# M_B_adapter.net
KiCad netlist of a schematic drawn in EAGLE
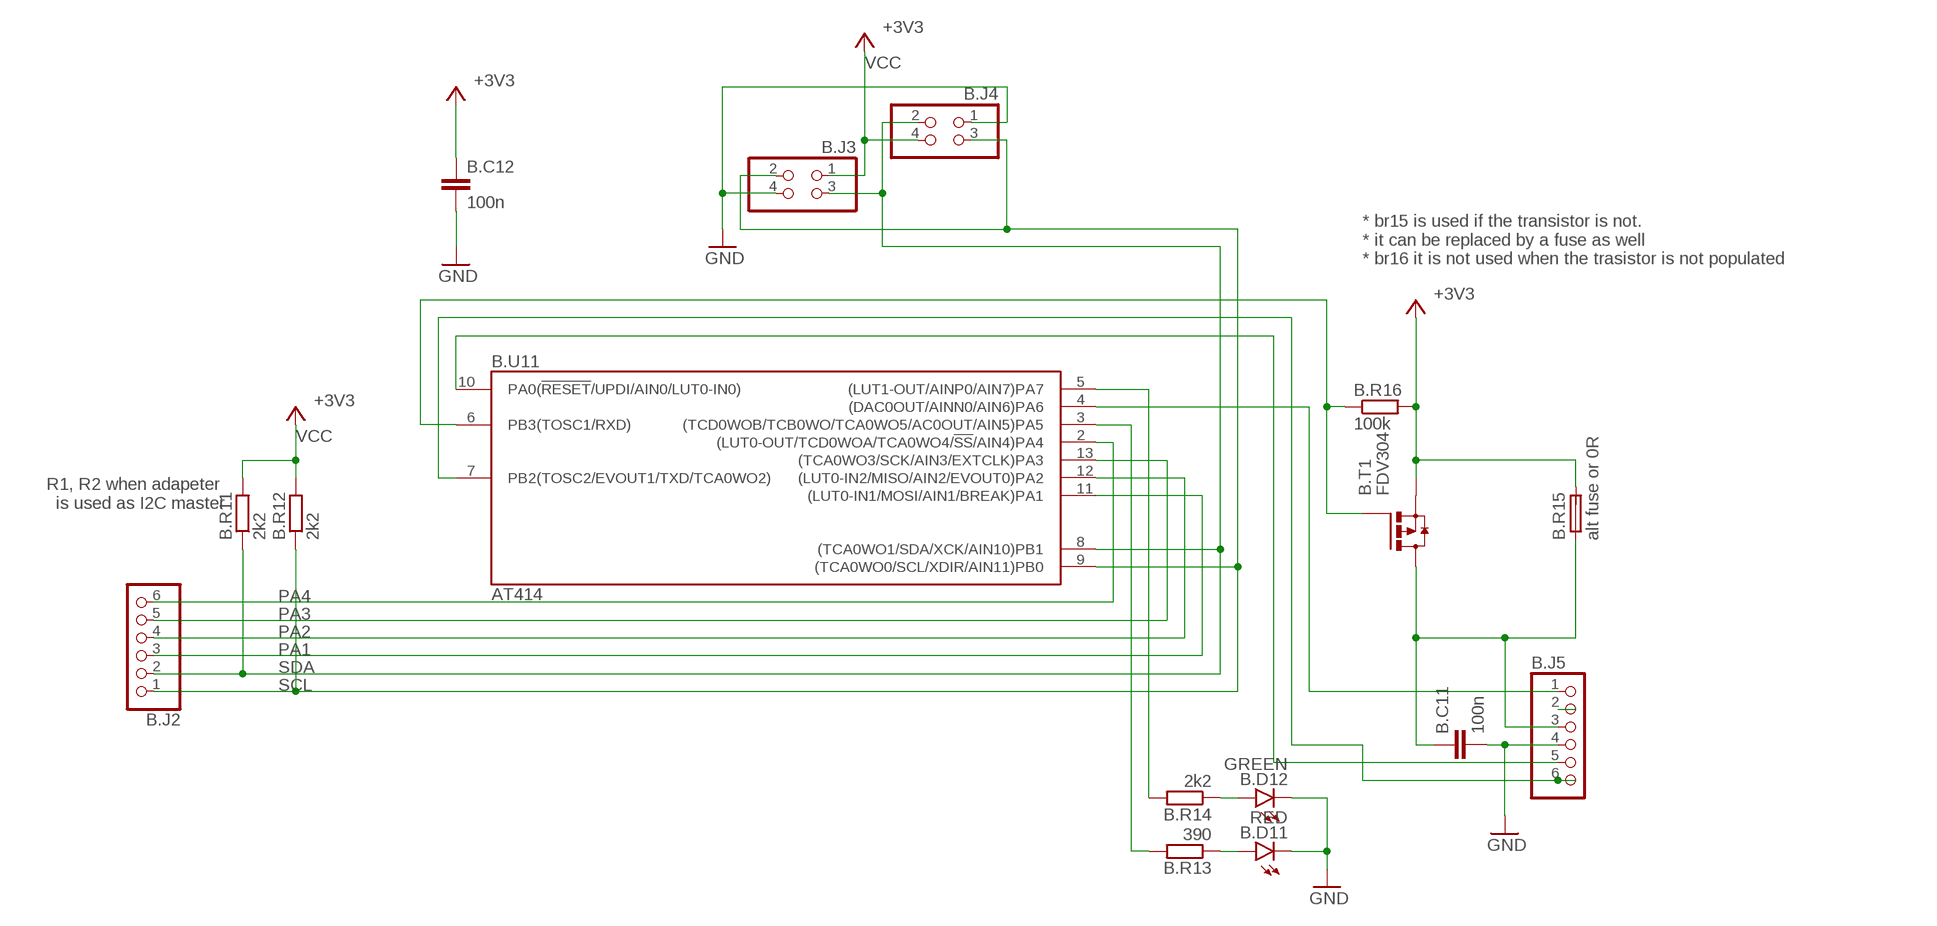
[diagram p0: schematic, sheet 1]

(export (version "E")
  (design (tool "Eeschema 10.0.6"))
  (components
    (comp (ref "B.C11")
      (value "100n")
      (footprint "eagle-import:C0603")
      (libsource (lib "eagle-import") (part "C-EUC0603"))
    )
    (comp (ref "B.C12")
      (value "100n")
      (footprint "eagle-import:C0603")
      (libsource (lib "eagle-import") (part "C-EUC0603"))
    )
    (comp (ref "B.D11")
      (value "RED")
      (footprint "eagle-import:CHIP-LED0603")
      (libsource (lib "eagle-import") (part "LEDCHIP-LED0603"))
    )
    (comp (ref "B.D12")
      (value "GREEN")
      (footprint "eagle-import:CHIP-LED0603")
      (libsource (lib "eagle-import") (part "LEDCHIP-LED0603"))
    )
    (comp (ref "B.J2")
      (value "PINHD-1X6")
      (footprint "eagle-import:1X06")
      (libsource (lib "eagle-import") (part "PINHD-1X6"))
    )
    (comp (ref "B.J3")
      (value "PINHD-2X2")
      (footprint "eagle-import:2X02")
      (libsource (lib "eagle-import") (part "PINHD-2X2"))
    )
    (comp (ref "B.J4")
      (value "PINHD-2X2")
      (footprint "eagle-import:2X02")
      (libsource (lib "eagle-import") (part "PINHD-2X2"))
    )
    (comp (ref "B.J5")
      (value "PINHD-1X6")
      (footprint "eagle-import:1X06")
      (libsource (lib "eagle-import") (part "PINHD-1X6"))
    )
    (comp (ref "B.R11")
      (value "2k2")
      (footprint "eagle-import:R0603")
      (libsource (lib "eagle-import") (part "R-EU_R0603"))
    )
    (comp (ref "B.R12")
      (value "2k2")
      (footprint "eagle-import:R0603")
      (libsource (lib "eagle-import") (part "R-EU_R0603"))
    )
    (comp (ref "B.R13")
      (value "390")
      (footprint "eagle-import:R0603")
      (libsource (lib "eagle-import") (part "R-EU_R0603"))
    )
    (comp (ref "B.R14")
      (value "2k2")
      (footprint "eagle-import:R0603")
      (libsource (lib "eagle-import") (part "R-EU_R0603"))
    )
    (comp (ref "B.R15")
      (value "alt fuse or 0R")
      (footprint "eagle-import:FUSE")
      (libsource (lib "eagle-import") (part "FUSE"))
    )
    (comp (ref "B.R16")
      (value "100k")
      (footprint "eagle-import:R0603")
      (libsource (lib "eagle-import") (part "R-EU_R0603"))
    )
    (comp (ref "B.T1")
      (value "FDV304")
      (footprint "eagle-import:SO23")
      (libsource (lib "eagle-import") (part "P-MOSFET"))
    )
    (comp (ref "B.U11")
      (value "AT414")
      (footprint "eagle-import:SO14")
      (libsource (lib "eagle-import") (part "ATTINY14-SSN4"))
    )
  )
  (nets
    (net (code "1") (name "+3V3") (class "Default")
      (node (ref "B.C12") (pin "1") (pinfunction "1_1") (pintype "passive"))
      (node (ref "B.J3") (pin "1") (pinfunction "1_1") (pintype "passive"))
      (node (ref "B.J4") (pin "4") (pinfunction "4_4") (pintype "passive"))
      (node (ref "B.R11") (pin "2") (pinfunction "2_2") (pintype "passive"))
      (node (ref "B.R12") (pin "2") (pinfunction "2_2") (pintype "passive"))
      (node (ref "B.R15") (pin "2") (pinfunction "2_2") (pintype "passive"))
      (node (ref "B.R16") (pin "2") (pinfunction "2_2") (pintype "passive"))
      (node (ref "B.T1") (pin "S") (pinfunction "S_S") (pintype "passive"))
    )
    (net (code "2") (name "/PA1") (class "Default")
      (node (ref "B.J2") (pin "3") (pinfunction "3_3") (pintype "passive"))
      (node (ref "B.U11") (pin "11") (pinfunction "(LUT0-IN1/MOSI/AIN1/BREAK)PA1_11") (pintype "bidirectional"))
    )
    (net (code "3") (name "/PA2") (class "Default")
      (node (ref "B.J2") (pin "4") (pinfunction "4_4") (pintype "passive"))
      (node (ref "B.U11") (pin "12") (pinfunction "(LUT0-IN2/MISO/AIN2/EVOUT0)PA2_12") (pintype "bidirectional"))
    )
    (net (code "4") (name "/PA3") (class "Default")
      (node (ref "B.J2") (pin "5") (pinfunction "5_5") (pintype "passive"))
      (node (ref "B.U11") (pin "13") (pinfunction "(TCA0WO3/SCK/AIN3/EXTCLK)PA3_13") (pintype "bidirectional"))
    )
    (net (code "5") (name "/PA4") (class "Default")
      (node (ref "B.J2") (pin "6") (pinfunction "6_6") (pintype "passive"))
      (node (ref "B.U11") (pin "2") (pinfunction "(LUT0-OUT/TCD0WOA/TCA0WO4/~{SS}/AIN4)PA4_2") (pintype "bidirectional"))
    )
    (net (code "6") (name "/SCL") (class "Default")
      (node (ref "B.J2") (pin "1") (pinfunction "1_1") (pintype "passive"))
      (node (ref "B.J3") (pin "2") (pinfunction "2_2") (pintype "passive"))
      (node (ref "B.J4") (pin "3") (pinfunction "3_3") (pintype "passive"))
      (node (ref "B.R12") (pin "1") (pinfunction "1_1") (pintype "passive"))
      (node (ref "B.U11") (pin "9") (pinfunction "(TCA0WO0/SCL/XDIR/AIN11)PB0_9") (pintype "bidirectional"))
    )
    (net (code "7") (name "/SDA") (class "Default")
      (node (ref "B.J2") (pin "2") (pinfunction "2_2") (pintype "passive"))
      (node (ref "B.J3") (pin "3") (pinfunction "3_3") (pintype "passive"))
      (node (ref "B.J4") (pin "2") (pinfunction "2_2") (pintype "passive"))
      (node (ref "B.R11") (pin "1") (pinfunction "1_1") (pintype "passive"))
      (node (ref "B.U11") (pin "8") (pinfunction "(TCA0WO1/SDA/XCK/AIN10)PB1_8") (pintype "bidirectional"))
    )
    (net (code "8") (name "GND") (class "Default")
      (node (ref "B.C11") (pin "2") (pinfunction "2_2") (pintype "passive"))
      (node (ref "B.C12") (pin "2") (pinfunction "2_2") (pintype "passive"))
      (node (ref "B.D11") (pin "C1") (pinfunction "C_C1") (pintype "passive"))
      (node (ref "B.D12") (pin "C1") (pinfunction "C_C1") (pintype "passive"))
      (node (ref "B.J3") (pin "4") (pinfunction "4_4") (pintype "passive"))
      (node (ref "B.J4") (pin "1") (pinfunction "1_1") (pintype "passive"))
      (node (ref "B.J5") (pin "4") (pinfunction "4_4") (pintype "passive"))
    )
    (net (code "9") (name "Net-(B.C11-Pad1)") (class "Default")
      (node (ref "B.C11") (pin "1") (pinfunction "1_1") (pintype "passive"))
      (node (ref "B.J5") (pin "3") (pinfunction "3_3") (pintype "passive"))
      (node (ref "B.R15") (pin "1") (pinfunction "1_1") (pintype "passive"))
      (node (ref "B.T1") (pin "D") (pinfunction "D_D") (pintype "passive"))
    )
    (net (code "10") (name "Net-(B.D11-A)") (class "Default")
      (node (ref "B.D11") (pin "A1") (pinfunction "A_A1") (pintype "passive"))
      (node (ref "B.R13") (pin "1") (pinfunction "1_1") (pintype "passive"))
    )
    (net (code "11") (name "Net-(B.D12-A)") (class "Default")
      (node (ref "B.D12") (pin "A1") (pinfunction "A_A1") (pintype "passive"))
      (node (ref "B.R14") (pin "1") (pinfunction "1_1") (pintype "passive"))
    )
    (net (code "12") (name "Net-(B.U11A-(DAC0OUT{slash}AINN0{slash}AIN6)PA6)") (class "Default")
      (node (ref "B.J5") (pin "1") (pinfunction "1_1") (pintype "passive"))
      (node (ref "B.U11") (pin "4") (pinfunction "(DAC0OUT/AINN0/AIN6)PA6_4") (pintype "bidirectional"))
    )
    (net (code "13") (name "Net-(B.U11A-(LUT1-OUT{slash}AINP0{slash}AIN7)PA7)") (class "Default")
      (node (ref "B.R14") (pin "2") (pinfunction "2_2") (pintype "passive"))
      (node (ref "B.U11") (pin "5") (pinfunction "(LUT1-OUT/AINP0/AIN7)PA7_5") (pintype "bidirectional"))
    )
    (net (code "14") (name "Net-(B.U11A-(TCD0WOB{slash}TCB0WO{slash}TCA0WO5{slash}AC0OUT{slash}AIN5)PA5)") (class "Default")
      (node (ref "B.R13") (pin "2") (pinfunction "2_2") (pintype "passive"))
      (node (ref "B.U11") (pin "3") (pinfunction "(TCD0WOB/TCB0WO/TCA0WO5/AC0OUT/AIN5)PA5_3") (pintype "bidirectional"))
    )
    (net (code "15") (name "Net-(B.U11A-PA0(~{RESET}{slash}UPDI{slash}AIN0{slash}LUT0-IN0))") (class "Default")
      (node (ref "B.J5") (pin "5") (pinfunction "5_5") (pintype "passive"))
      (node (ref "B.U11") (pin "10") (pinfunction "PA0(~{RESET}/UPDI/AIN0/LUT0-IN0)_10") (pintype "bidirectional"))
    )
    (net (code "16") (name "Net-(B.U11A-PB2(TOSC2{slash}EVOUT1{slash}TXD{slash}TCA0WO2))") (class "Default")
      (node (ref "B.J5") (pin "6") (pinfunction "6_6") (pintype "passive"))
      (node (ref "B.U11") (pin "7") (pinfunction "PB2(TOSC2/EVOUT1/TXD/TCA0WO2)_7") (pintype "bidirectional"))
    )
    (net (code "17") (name "Net-(B.U11A-PB3(TOSC1{slash}RXD))") (class "Default")
      (node (ref "B.R16") (pin "1") (pinfunction "1_1") (pintype "passive"))
      (node (ref "B.T1") (pin "G") (pinfunction "G_G") (pintype "passive"))
      (node (ref "B.U11") (pin "6") (pinfunction "PB3(TOSC1/RXD)_6") (pintype "bidirectional"))
    )
    (net (code "18") (name "unconnected-(B.J5-Pad2)") (class "Default")
      (node (ref "B.J5") (pin "2") (pinfunction "2_2") (pintype "passive"))
    )
  )
)
